# sd-logger.net
KiCad netlist of a schematic drawn in EAGLE
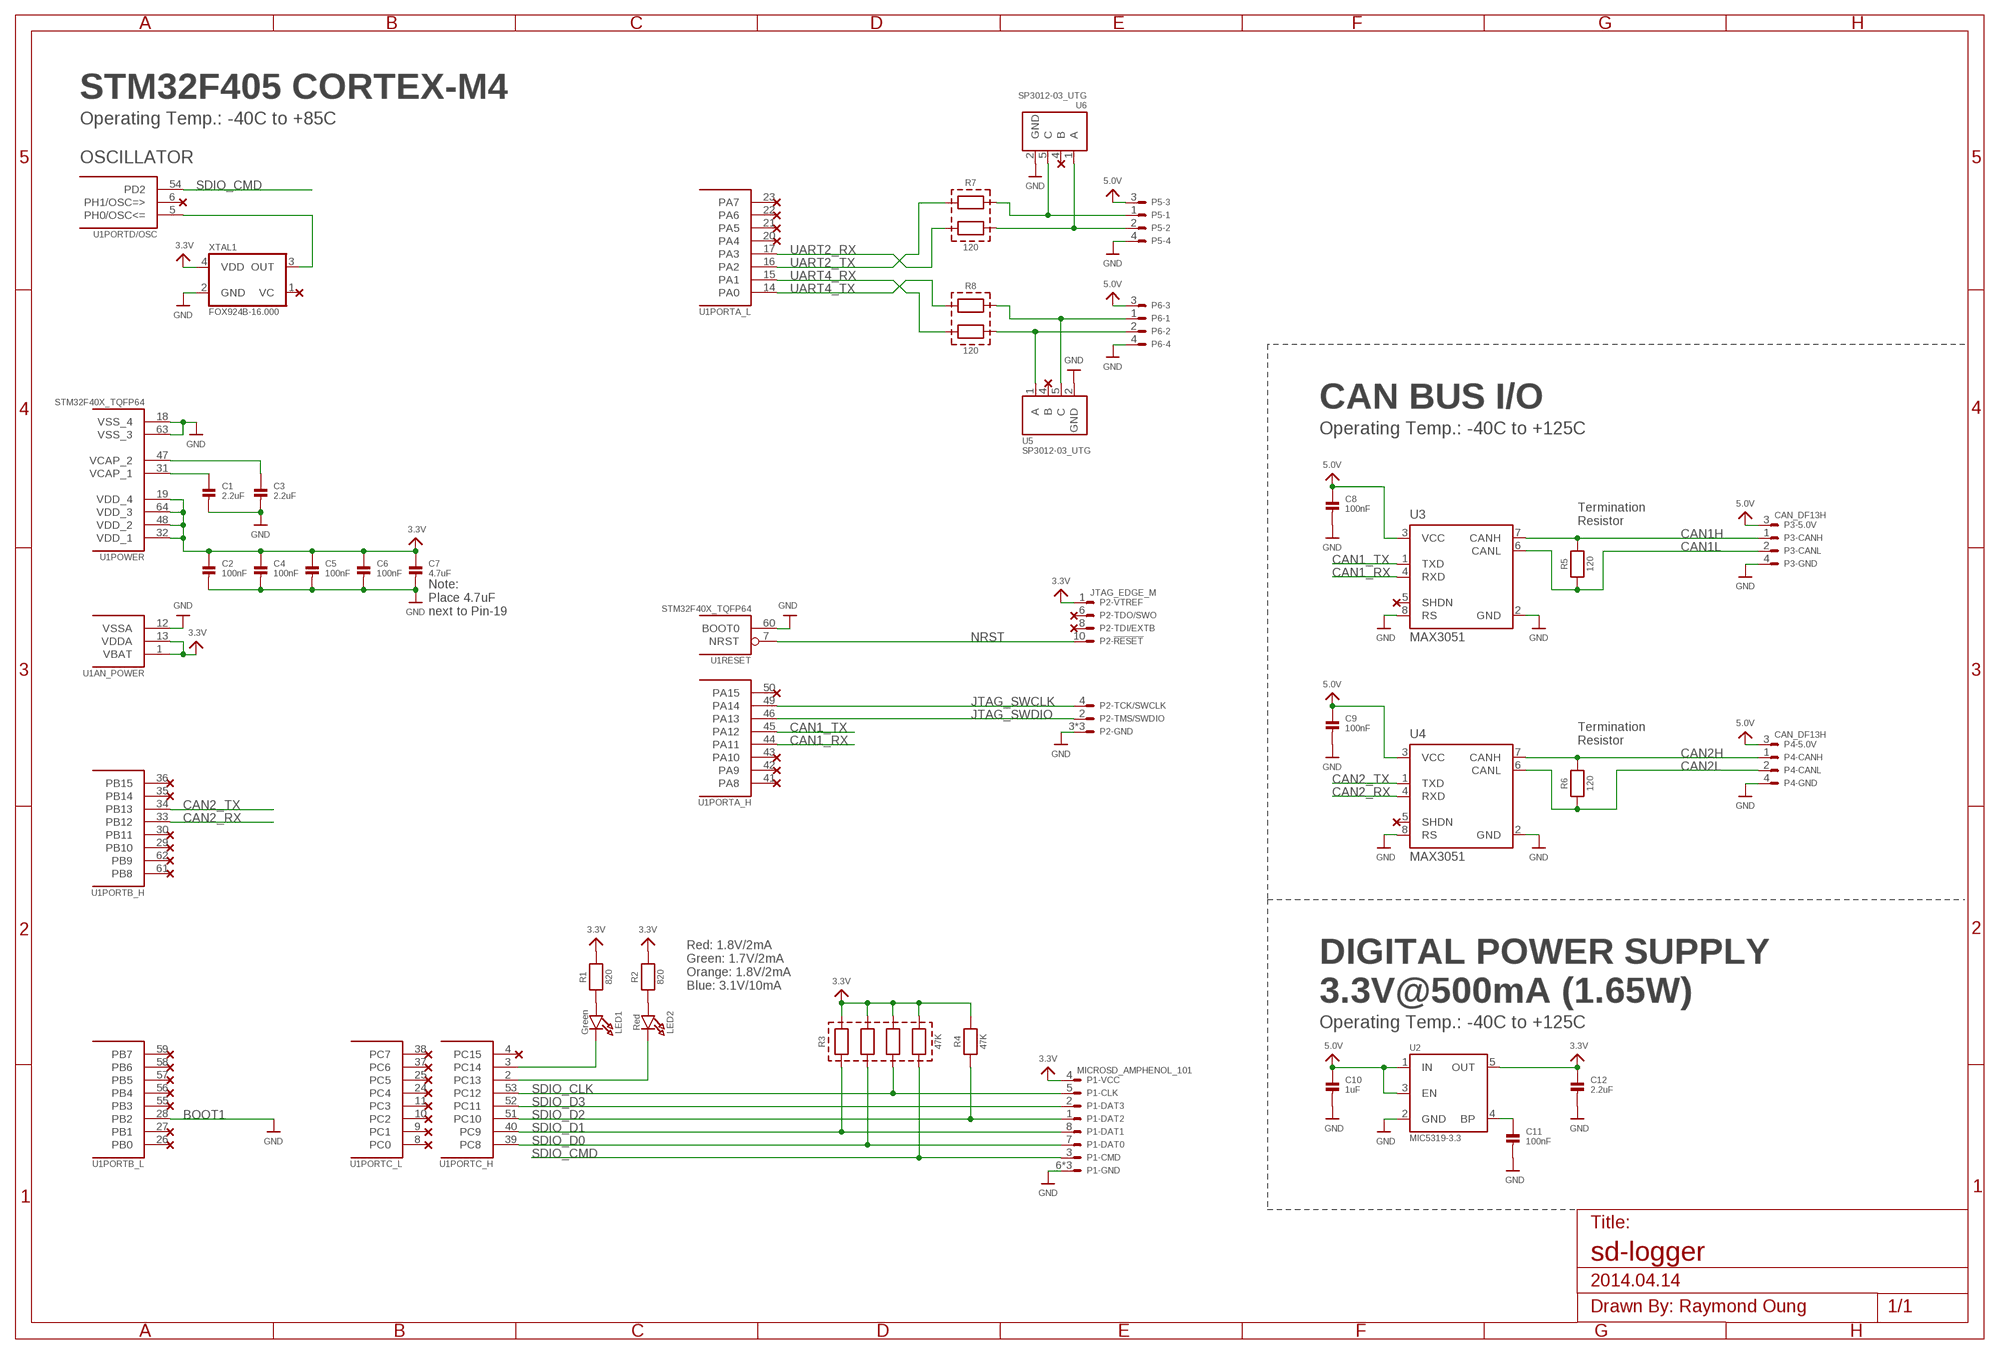
[diagram p0: schematic, sheet 1]

(export (version "E")
  (design (tool "Eeschema 10.0.6"))
  (components
    (comp (ref "C1")
      (value "2.2uF")
      (footprint "eagle-import:0402")
      (libsource (lib "eagle-import") (part "CAP_CERAMIC0402"))
    )
    (comp (ref "C2")
      (value "100nF")
      (footprint "eagle-import:0402")
      (libsource (lib "eagle-import") (part "CAP_CERAMIC0402"))
    )
    (comp (ref "C3")
      (value "2.2uF")
      (footprint "eagle-import:0402")
      (libsource (lib "eagle-import") (part "CAP_CERAMIC0402"))
    )
    (comp (ref "C4")
      (value "100nF")
      (footprint "eagle-import:0402")
      (libsource (lib "eagle-import") (part "CAP_CERAMIC0402"))
    )
    (comp (ref "C5")
      (value "100nF")
      (footprint "eagle-import:0402")
      (libsource (lib "eagle-import") (part "CAP_CERAMIC0402"))
    )
    (comp (ref "C6")
      (value "100nF")
      (footprint "eagle-import:0402")
      (libsource (lib "eagle-import") (part "CAP_CERAMIC0402"))
    )
    (comp (ref "C7")
      (value "4.7uF")
      (footprint "eagle-import:0402")
      (libsource (lib "eagle-import") (part "CAP_CERAMIC0402"))
    )
    (comp (ref "C8")
      (value "100nF")
      (footprint "eagle-import:0402")
      (libsource (lib "eagle-import") (part "CAP_CERAMIC0402"))
    )
    (comp (ref "C9")
      (value "100nF")
      (footprint "eagle-import:0402")
      (libsource (lib "eagle-import") (part "CAP_CERAMIC0402"))
    )
    (comp (ref "C10")
      (value "1uF")
      (footprint "eagle-import:0402")
      (libsource (lib "eagle-import") (part "CAP_CERAMIC0402"))
    )
    (comp (ref "C11")
      (value "100nF")
      (footprint "eagle-import:0402")
      (libsource (lib "eagle-import") (part "CAP_CERAMIC0402"))
    )
    (comp (ref "C12")
      (value "2.2uF")
      (footprint "eagle-import:0402")
      (libsource (lib "eagle-import") (part "CAP_CERAMIC0402"))
    )
    (comp (ref "LED1")
      (value "Green")
      (footprint "eagle-import:CHIPLED_0603")
      (libsource (lib "eagle-import") (part "LED_0603"))
    )
    (comp (ref "LED2")
      (value "Red")
      (footprint "eagle-import:CHIPLED_0603")
      (libsource (lib "eagle-import") (part "LED_0603"))
    )
    (comp (ref "P1")
      (value "MICROSD_AMPHENOL_101")
      (footprint "eagle-import:AMPHENOL_101-00660-68")
      (libsource (lib "eagle-import") (part "MICROSD_AMPHENOL_101"))
    )
    (comp (ref "P2")
      (value "JTAG_EDGE_M")
      (footprint "eagle-import:FTSH-105-01-XXX-DV-EDGE")
      (libsource (lib "eagle-import") (part "JTAG_EDGE_M"))
    )
    (comp (ref "P3")
      (value "CAN_DF13H")
      (footprint "eagle-import:DF13A-4P-1.25H")
      (libsource (lib "eagle-import") (part "CAN_DF13H"))
    )
    (comp (ref "P4")
      (value "CAN_DF13H")
      (footprint "eagle-import:DF13A-4P-1.25H")
      (libsource (lib "eagle-import") (part "CAN_DF13H"))
    )
    (comp (ref "P5")
      (value "M04_DF13H")
      (footprint "eagle-import:DF13A-4P-1.25H")
      (libsource (lib "eagle-import") (part "M04_DF13H"))
    )
    (comp (ref "P6")
      (value "M04_DF13H")
      (footprint "eagle-import:DF13A-4P-1.25H")
      (libsource (lib "eagle-import") (part "M04_DF13H"))
    )
    (comp (ref "R1")
      (value "820")
      (footprint "eagle-import:0402")
      (libsource (lib "eagle-import") (part "RESISTOR0402"))
    )
    (comp (ref "R2")
      (value "820")
      (footprint "eagle-import:0402")
      (libsource (lib "eagle-import") (part "RESISTOR0402"))
    )
    (comp (ref "R3")
      (value "47K")
      (footprint "eagle-import:EXBV8V")
      (libsource (lib "eagle-import") (part "RESISTOR4_0603X4"))
    )
    (comp (ref "R4")
      (value "47K")
      (footprint "eagle-import:0402")
      (libsource (lib "eagle-import") (part "RESISTOR0402"))
    )
    (comp (ref "R5")
      (value "120")
      (footprint "eagle-import:0603")
      (libsource (lib "eagle-import") (part "RESISTOR0603"))
    )
    (comp (ref "R6")
      (value "120")
      (footprint "eagle-import:0603")
      (libsource (lib "eagle-import") (part "RESISTOR0603"))
    )
    (comp (ref "R7")
      (value "120")
      (footprint "eagle-import:EXBV4V")
      (libsource (lib "eagle-import") (part "RESISTOR2_0603X2"))
    )
    (comp (ref "R8")
      (value "120")
      (footprint "eagle-import:EXBV4V")
      (libsource (lib "eagle-import") (part "RESISTOR2_0603X2"))
    )
    (comp (ref "U1")
      (value "STM32F40X_TQFP64")
      (footprint "eagle-import:TQFP64")
      (libsource (lib "eagle-import") (part "STM32F40X_TQFP64"))
    )
    (comp (ref "U2")
      (value "MIC5319-3.3")
      (footprint "eagle-import:SOT23-5")
      (libsource (lib "eagle-import") (part "MIC5319-3.3"))
    )
    (comp (ref "U3")
      (value "MAX3051")
      (footprint "eagle-import:SOT23-8")
      (libsource (lib "eagle-import") (part "MAX3051"))
    )
    (comp (ref "U4")
      (value "MAX3051")
      (footprint "eagle-import:SOT23-8")
      (libsource (lib "eagle-import") (part "MAX3051"))
    )
    (comp (ref "U5")
      (value "SP3012-03_UTG")
      (footprint "eagle-import:UDFN06")
      (libsource (lib "eagle-import") (part "SP3012-03_UTG"))
    )
    (comp (ref "U6")
      (value "SP3012-03_UTG")
      (footprint "eagle-import:UDFN06")
      (libsource (lib "eagle-import") (part "SP3012-03_UTG"))
    )
    (comp (ref "XTAL1")
      (value "FOX924B-16.000")
      (footprint "eagle-import:OSCILLATOR-5.0X3.2")
      (libsource (lib "eagle-import") (part "TCXO_5.0X3.2"))
    )
  )
  (nets
    (net (code "1") (name "/CAN1H") (class "Default")
      (node (ref "P3") (pin "1") (pinfunction "S_1") (pintype "passive"))
      (node (ref "R5") (pin "2") (pinfunction "2_2") (pintype "passive"))
      (node (ref "U3") (pin "7") (pinfunction "CANH_7") (pintype "bidirectional"))
    )
    (net (code "2") (name "/CAN1L") (class "Default")
      (node (ref "P3") (pin "2") (pinfunction "S_2") (pintype "passive"))
      (node (ref "R5") (pin "1") (pinfunction "1_1") (pintype "passive"))
      (node (ref "U3") (pin "6") (pinfunction "CANL_6") (pintype "bidirectional"))
    )
    (net (code "3") (name "/CAN1_RX") (class "Default")
      (node (ref "U1") (pin "44") (pinfunction "PA11_44") (pintype "bidirectional"))
      (node (ref "U3") (pin "4") (pinfunction "RXD_4") (pintype "bidirectional"))
    )
    (net (code "4") (name "/CAN1_TX") (class "Default")
      (node (ref "U1") (pin "45") (pinfunction "PA12_45") (pintype "bidirectional"))
      (node (ref "U3") (pin "1") (pinfunction "TXD_1") (pintype "bidirectional"))
    )
    (net (code "5") (name "/CAN2H") (class "Default")
      (node (ref "P4") (pin "1") (pinfunction "S_1") (pintype "passive"))
      (node (ref "R6") (pin "2") (pinfunction "2_2") (pintype "passive"))
      (node (ref "U4") (pin "7") (pinfunction "CANH_7") (pintype "bidirectional"))
    )
    (net (code "6") (name "/CAN2L") (class "Default")
      (node (ref "P4") (pin "2") (pinfunction "S_2") (pintype "passive"))
      (node (ref "R6") (pin "1") (pinfunction "1_1") (pintype "passive"))
      (node (ref "U4") (pin "6") (pinfunction "CANL_6") (pintype "bidirectional"))
    )
    (net (code "7") (name "/CAN2_RX") (class "Default")
      (node (ref "U1") (pin "33") (pinfunction "PB12_33") (pintype "bidirectional"))
      (node (ref "U4") (pin "4") (pinfunction "RXD_4") (pintype "bidirectional"))
    )
    (net (code "8") (name "/CAN2_TX") (class "Default")
      (node (ref "U1") (pin "34") (pinfunction "PB13_34") (pintype "bidirectional"))
      (node (ref "U4") (pin "1") (pinfunction "TXD_1") (pintype "bidirectional"))
    )
    (net (code "9") (name "/JTAG_SWCLK") (class "Default")
      (node (ref "P2") (pin "4") (pinfunction "S_4") (pintype "passive"))
      (node (ref "U1") (pin "49") (pinfunction "PA14_49") (pintype "bidirectional"))
    )
    (net (code "10") (name "/JTAG_SWDIO") (class "Default")
      (node (ref "P2") (pin "2") (pinfunction "S_2") (pintype "passive"))
      (node (ref "U1") (pin "46") (pinfunction "PA13_46") (pintype "bidirectional"))
    )
    (net (code "11") (name "/NRST") (class "Default")
      (node (ref "P2") (pin "10") (pinfunction "S_10") (pintype "passive"))
      (node (ref "U1") (pin "7") (pinfunction "NRST_7") (pintype "input"))
    )
    (net (code "12") (name "/SDIO_CLK") (class "Default")
      (node (ref "P1") (pin "5") (pinfunction "S_5") (pintype "passive"))
      (node (ref "R3") (pin "3") (pinfunction "3_3") (pintype "passive"))
      (node (ref "U1") (pin "53") (pinfunction "PC12_53") (pintype "bidirectional"))
    )
    (net (code "13") (name "/SDIO_CMD") (class "Default")
      (node (ref "P1") (pin "3") (pinfunction "S_3") (pintype "passive"))
      (node (ref "R3") (pin "4") (pinfunction "4_4") (pintype "passive"))
      (node (ref "U1") (pin "54") (pinfunction "PD2_54") (pintype "bidirectional"))
    )
    (net (code "14") (name "/SDIO_D0") (class "Default")
      (node (ref "P1") (pin "7") (pinfunction "S_7") (pintype "passive"))
      (node (ref "R3") (pin "2") (pinfunction "2_2") (pintype "passive"))
      (node (ref "U1") (pin "39") (pinfunction "PC8_39") (pintype "bidirectional"))
    )
    (net (code "15") (name "/SDIO_D1") (class "Default")
      (node (ref "P1") (pin "8") (pinfunction "S_8") (pintype "passive"))
      (node (ref "R3") (pin "1") (pinfunction "1_1") (pintype "passive"))
      (node (ref "U1") (pin "40") (pinfunction "PC9_40") (pintype "bidirectional"))
    )
    (net (code "16") (name "/SDIO_D2") (class "Default")
      (node (ref "P1") (pin "1") (pinfunction "S_1") (pintype "passive"))
      (node (ref "R4") (pin "1") (pinfunction "1_1") (pintype "passive"))
      (node (ref "U1") (pin "51") (pinfunction "PC10_51") (pintype "bidirectional"))
    )
    (net (code "17") (name "/SDIO_D3") (class "Default")
      (node (ref "P1") (pin "2") (pinfunction "S_2") (pintype "passive"))
      (node (ref "U1") (pin "52") (pinfunction "PC11_52") (pintype "bidirectional"))
    )
    (net (code "18") (name "/UART2_RX") (class "Default")
      (node (ref "R7") (pin "2") (pinfunction "2_2") (pintype "passive"))
      (node (ref "U1") (pin "17") (pinfunction "PA3_17") (pintype "bidirectional"))
    )
    (net (code "19") (name "/UART2_TX") (class "Default")
      (node (ref "R7") (pin "1") (pinfunction "1_1") (pintype "passive"))
      (node (ref "U1") (pin "16") (pinfunction "PA2_16") (pintype "bidirectional"))
    )
    (net (code "20") (name "/UART4_RX") (class "Default")
      (node (ref "R8") (pin "2") (pinfunction "2_2") (pintype "passive"))
      (node (ref "U1") (pin "15") (pinfunction "PA1_15") (pintype "bidirectional"))
    )
    (net (code "21") (name "/UART4_TX") (class "Default")
      (node (ref "R8") (pin "1") (pinfunction "1_1") (pintype "passive"))
      (node (ref "U1") (pin "14") (pinfunction "PA0_14") (pintype "bidirectional"))
    )
    (net (code "22") (name "3.3V") (class "Default")
      (node (ref "C12") (pin "1") (pinfunction "P$1_1") (pintype "passive"))
      (node (ref "C2") (pin "1") (pinfunction "P$1_1") (pintype "passive"))
      (node (ref "C4") (pin "1") (pinfunction "P$1_1") (pintype "passive"))
      (node (ref "C5") (pin "1") (pinfunction "P$1_1") (pintype "passive"))
      (node (ref "C6") (pin "1") (pinfunction "P$1_1") (pintype "passive"))
      (node (ref "C7") (pin "1") (pinfunction "P$1_1") (pintype "passive"))
      (node (ref "P1") (pin "4") (pinfunction "S_4") (pintype "passive"))
      (node (ref "P2") (pin "1") (pinfunction "S_1") (pintype "passive"))
      (node (ref "R1") (pin "2") (pinfunction "2_2") (pintype "passive"))
      (node (ref "R2") (pin "2") (pinfunction "2_2") (pintype "passive"))
      (node (ref "R3") (pin "5") (pinfunction "5_5") (pintype "passive"))
      (node (ref "R3") (pin "6") (pinfunction "6_6") (pintype "passive"))
      (node (ref "R3") (pin "7") (pinfunction "7_7") (pintype "passive"))
      (node (ref "R3") (pin "8") (pinfunction "8_8") (pintype "passive"))
      (node (ref "R4") (pin "2") (pinfunction "2_2") (pintype "passive"))
      (node (ref "U1") (pin "1") (pinfunction "VBAT_1") (pintype "power_in"))
      (node (ref "U1") (pin "13") (pinfunction "VDDA_13") (pintype "power_in"))
      (node (ref "U1") (pin "19") (pinfunction "VDD_4_19") (pintype "power_in"))
      (node (ref "U1") (pin "32") (pinfunction "VDD_1_32") (pintype "power_in"))
      (node (ref "U1") (pin "48") (pinfunction "VDD_2_48") (pintype "power_in"))
      (node (ref "U1") (pin "64") (pinfunction "VDD_3_64") (pintype "power_in"))
      (node (ref "U2") (pin "5") (pinfunction "OUT_5") (pintype "bidirectional"))
      (node (ref "XTAL1") (pin "4") (pinfunction "VDD_4") (pintype "bidirectional"))
    )
    (net (code "23") (name "5.0V") (class "Default")
      (node (ref "C10") (pin "1") (pinfunction "P$1_1") (pintype "passive"))
      (node (ref "C8") (pin "1") (pinfunction "P$1_1") (pintype "passive"))
      (node (ref "C9") (pin "1") (pinfunction "P$1_1") (pintype "passive"))
      (node (ref "P3") (pin "3") (pinfunction "S_3") (pintype "passive"))
      (node (ref "P4") (pin "3") (pinfunction "S_3") (pintype "passive"))
      (node (ref "P5") (pin "3") (pinfunction "S_3") (pintype "passive"))
      (node (ref "P6") (pin "3") (pinfunction "S_3") (pintype "passive"))
      (node (ref "U2") (pin "1") (pinfunction "IN_1") (pintype "bidirectional"))
      (node (ref "U2") (pin "3") (pinfunction "EN_3") (pintype "bidirectional"))
      (node (ref "U3") (pin "3") (pinfunction "VCC_3") (pintype "bidirectional"))
      (node (ref "U4") (pin "3") (pinfunction "VCC_3") (pintype "bidirectional"))
    )
    (net (code "24") (name "GND") (class "Default")
      (node (ref "C1") (pin "2") (pinfunction "P$2_2") (pintype "passive"))
      (node (ref "C10") (pin "2") (pinfunction "P$2_2") (pintype "passive"))
      (node (ref "C11") (pin "2") (pinfunction "P$2_2") (pintype "passive"))
      (node (ref "C12") (pin "2") (pinfunction "P$2_2") (pintype "passive"))
      (node (ref "C2") (pin "2") (pinfunction "P$2_2") (pintype "passive"))
      (node (ref "C3") (pin "2") (pinfunction "P$2_2") (pintype "passive"))
      (node (ref "C4") (pin "2") (pinfunction "P$2_2") (pintype "passive"))
      (node (ref "C5") (pin "2") (pinfunction "P$2_2") (pintype "passive"))
      (node (ref "C6") (pin "2") (pinfunction "P$2_2") (pintype "passive"))
      (node (ref "C7") (pin "2") (pinfunction "P$2_2") (pintype "passive"))
      (node (ref "C8") (pin "2") (pinfunction "P$2_2") (pintype "passive"))
      (node (ref "C9") (pin "2") (pinfunction "P$2_2") (pintype "passive"))
      (node (ref "P1") (pin "6") (pinfunction "S_6") (pintype "passive"))
      (node (ref "P1") (pin "GND1") (pinfunction "S_GND1") (pintype "passive"))
      (node (ref "P1") (pin "GND3") (pinfunction "S_GND3") (pintype "passive"))
      (node (ref "P2") (pin "3") (pinfunction "S_3") (pintype "passive"))
      (node (ref "P2") (pin "5") (pinfunction "S_5") (pintype "passive"))
      (node (ref "P2") (pin "9") (pinfunction "S_9") (pintype "passive"))
      (node (ref "P3") (pin "4") (pinfunction "S_4") (pintype "passive"))
      (node (ref "P4") (pin "4") (pinfunction "S_4") (pintype "passive"))
      (node (ref "P5") (pin "4") (pinfunction "S_4") (pintype "passive"))
      (node (ref "P6") (pin "4") (pinfunction "S_4") (pintype "passive"))
      (node (ref "U1") (pin "12") (pinfunction "VSSA_12") (pintype "power_in"))
      (node (ref "U1") (pin "18") (pinfunction "VSS_4_18") (pintype "power_in"))
      (node (ref "U1") (pin "28") (pinfunction "PB2_28") (pintype "bidirectional"))
      (node (ref "U1") (pin "60") (pinfunction "BOOT0_60") (pintype "input"))
      (node (ref "U1") (pin "63") (pinfunction "VSS_3_63") (pintype "power_in"))
      (node (ref "U2") (pin "2") (pinfunction "GND_2") (pintype "bidirectional"))
      (node (ref "U3") (pin "2") (pinfunction "GND_2") (pintype "bidirectional"))
      (node (ref "U3") (pin "8") (pinfunction "RS_8") (pintype "bidirectional"))
      (node (ref "U4") (pin "2") (pinfunction "GND_2") (pintype "bidirectional"))
      (node (ref "U4") (pin "8") (pinfunction "RS_8") (pintype "bidirectional"))
      (node (ref "U5") (pin "2") (pinfunction "GND_2") (pintype "power_in"))
      (node (ref "U6") (pin "2") (pinfunction "GND_2") (pintype "power_in"))
      (node (ref "XTAL1") (pin "2") (pinfunction "GND_2") (pintype "bidirectional"))
    )
    (net (code "25") (name "Net-(C1-P$1)") (class "Default")
      (node (ref "C1") (pin "1") (pinfunction "P$1_1") (pintype "passive"))
      (node (ref "U1") (pin "31") (pinfunction "VCAP_1_31") (pintype "power_in"))
    )
    (net (code "26") (name "Net-(C3-P$1)") (class "Default")
      (node (ref "C3") (pin "1") (pinfunction "P$1_1") (pintype "passive"))
      (node (ref "U1") (pin "47") (pinfunction "VCAP_2_47") (pintype "power_in"))
    )
    (net (code "27") (name "Net-(C11-P$1)") (class "Default")
      (node (ref "C11") (pin "1") (pinfunction "P$1_1") (pintype "passive"))
      (node (ref "U2") (pin "4") (pinfunction "BP_4") (pintype "bidirectional"))
    )
    (net (code "28") (name "Net-(LED1-PadA)") (class "Default")
      (node (ref "LED1") (pin "A") (pinfunction "A_A") (pintype "passive"))
      (node (ref "R1") (pin "1") (pinfunction "1_1") (pintype "passive"))
    )
    (net (code "29") (name "Net-(LED2-PadA)") (class "Default")
      (node (ref "LED2") (pin "A") (pinfunction "A_A") (pintype "passive"))
      (node (ref "R2") (pin "1") (pinfunction "1_1") (pintype "passive"))
    )
    (net (code "30") (name "Net-(P5A-S)") (class "Default")
      (node (ref "P5") (pin "1") (pinfunction "S_1") (pintype "passive"))
      (node (ref "R7") (pin "4") (pinfunction "4_4") (pintype "passive"))
      (node (ref "U6") (pin "5") (pinfunction "C_5") (pintype "bidirectional"))
    )
    (net (code "31") (name "Net-(P5B-S)") (class "Default")
      (node (ref "P5") (pin "2") (pinfunction "S_2") (pintype "passive"))
      (node (ref "R7") (pin "3") (pinfunction "3_3") (pintype "passive"))
      (node (ref "U6") (pin "1") (pinfunction "A_1") (pintype "bidirectional"))
    )
    (net (code "32") (name "Net-(P6A-S)") (class "Default")
      (node (ref "P6") (pin "1") (pinfunction "S_1") (pintype "passive"))
      (node (ref "R8") (pin "4") (pinfunction "4_4") (pintype "passive"))
      (node (ref "U5") (pin "5") (pinfunction "C_5") (pintype "bidirectional"))
    )
    (net (code "33") (name "Net-(P6B-S)") (class "Default")
      (node (ref "P6") (pin "2") (pinfunction "S_2") (pintype "passive"))
      (node (ref "R8") (pin "3") (pinfunction "3_3") (pintype "passive"))
      (node (ref "U5") (pin "1") (pinfunction "A_1") (pintype "bidirectional"))
    )
    (net (code "34") (name "Net-(U1F-PC13)") (class "Default")
      (node (ref "LED2") (pin "C") (pinfunction "C_C") (pintype "passive"))
      (node (ref "U1") (pin "2") (pinfunction "PC13_2") (pintype "bidirectional"))
    )
    (net (code "35") (name "Net-(U1F-PC14)") (class "Default")
      (node (ref "LED1") (pin "C") (pinfunction "C_C") (pintype "passive"))
      (node (ref "U1") (pin "3") (pinfunction "PC14_3") (pintype "bidirectional"))
    )
    (net (code "36") (name "Net-(U1H-PH0{slash}OSC<=)") (class "Default")
      (node (ref "U1") (pin "5") (pinfunction "PH0/OSC<=_5") (pintype "bidirectional"))
      (node (ref "XTAL1") (pin "3") (pinfunction "OUT_3") (pintype "bidirectional"))
    )
    (net (code "37") (name "unconnected-(P2D-S-Pad8)") (class "Default")
      (node (ref "P2") (pin "8") (pinfunction "S_8") (pintype "passive"))
    )
    (net (code "38") (name "unconnected-(P2E-S-Pad6)") (class "Default")
      (node (ref "P2") (pin "6") (pinfunction "S_6") (pintype "passive"))
    )
    (net (code "39") (name "unconnected-(U1B-PA8-Pad41)") (class "Default")
      (node (ref "U1") (pin "41") (pinfunction "PA8_41") (pintype "bidirectional"))
    )
    (net (code "40") (name "unconnected-(U1B-PA9-Pad42)") (class "Default")
      (node (ref "U1") (pin "42") (pinfunction "PA9_42") (pintype "bidirectional"))
    )
    (net (code "41") (name "unconnected-(U1B-PA10-Pad43)") (class "Default")
      (node (ref "U1") (pin "43") (pinfunction "PA10_43") (pintype "bidirectional"))
    )
    (net (code "42") (name "unconnected-(U1B-PA15-Pad50)") (class "Default")
      (node (ref "U1") (pin "50") (pinfunction "PA15_50") (pintype "bidirectional"))
    )
    (net (code "43") (name "unconnected-(U1C-PA4-Pad20)") (class "Default")
      (node (ref "U1") (pin "20") (pinfunction "PA4_20") (pintype "bidirectional"))
    )
    (net (code "44") (name "unconnected-(U1C-PA5-Pad21)") (class "Default")
      (node (ref "U1") (pin "21") (pinfunction "PA5_21") (pintype "bidirectional"))
    )
    (net (code "45") (name "unconnected-(U1C-PA6-Pad22)") (class "Default")
      (node (ref "U1") (pin "22") (pinfunction "PA6_22") (pintype "bidirectional"))
    )
    (net (code "46") (name "unconnected-(U1C-PA7-Pad23)") (class "Default")
      (node (ref "U1") (pin "23") (pinfunction "PA7_23") (pintype "bidirectional"))
    )
    (net (code "47") (name "unconnected-(U1D-PB8-Pad61)") (class "Default")
      (node (ref "U1") (pin "61") (pinfunction "PB8_61") (pintype "bidirectional"))
    )
    (net (code "48") (name "unconnected-(U1D-PB9-Pad62)") (class "Default")
      (node (ref "U1") (pin "62") (pinfunction "PB9_62") (pintype "bidirectional"))
    )
    (net (code "49") (name "unconnected-(U1D-PB10-Pad29)") (class "Default")
      (node (ref "U1") (pin "29") (pinfunction "PB10_29") (pintype "bidirectional"))
    )
    (net (code "50") (name "unconnected-(U1D-PB11-Pad30)") (class "Default")
      (node (ref "U1") (pin "30") (pinfunction "PB11_30") (pintype "bidirectional"))
    )
    (net (code "51") (name "unconnected-(U1D-PB14-Pad35)") (class "Default")
      (node (ref "U1") (pin "35") (pinfunction "PB14_35") (pintype "bidirectional"))
    )
    (net (code "52") (name "unconnected-(U1D-PB15-Pad36)") (class "Default")
      (node (ref "U1") (pin "36") (pinfunction "PB15_36") (pintype "bidirectional"))
    )
    (net (code "53") (name "unconnected-(U1E-PB0-Pad26)") (class "Default")
      (node (ref "U1") (pin "26") (pinfunction "PB0_26") (pintype "bidirectional"))
    )
    (net (code "54") (name "unconnected-(U1E-PB1-Pad27)") (class "Default")
      (node (ref "U1") (pin "27") (pinfunction "PB1_27") (pintype "bidirectional"))
    )
    (net (code "55") (name "unconnected-(U1E-PB3-Pad55)") (class "Default")
      (node (ref "U1") (pin "55") (pinfunction "PB3_55") (pintype "bidirectional"))
    )
    (net (code "56") (name "unconnected-(U1E-PB4-Pad56)") (class "Default")
      (node (ref "U1") (pin "56") (pinfunction "PB4_56") (pintype "bidirectional"))
    )
    (net (code "57") (name "unconnected-(U1E-PB5-Pad57)") (class "Default")
      (node (ref "U1") (pin "57") (pinfunction "PB5_57") (pintype "bidirectional"))
    )
    (net (code "58") (name "unconnected-(U1E-PB6-Pad58)") (class "Default")
      (node (ref "U1") (pin "58") (pinfunction "PB6_58") (pintype "bidirectional"))
    )
    (net (code "59") (name "unconnected-(U1E-PB7-Pad59)") (class "Default")
      (node (ref "U1") (pin "59") (pinfunction "PB7_59") (pintype "bidirectional"))
    )
    (net (code "60") (name "unconnected-(U1F-PC15-Pad4)") (class "Default")
      (node (ref "U1") (pin "4") (pinfunction "PC15_4") (pintype "bidirectional"))
    )
    (net (code "61") (name "unconnected-(U1G-PC0-Pad8)") (class "Default")
      (node (ref "U1") (pin "8") (pinfunction "PC0_8") (pintype "bidirectional"))
    )
    (net (code "62") (name "unconnected-(U1G-PC1-Pad9)") (class "Default")
      (node (ref "U1") (pin "9") (pinfunction "PC1_9") (pintype "bidirectional"))
    )
    (net (code "63") (name "unconnected-(U1G-PC2-Pad10)") (class "Default")
      (node (ref "U1") (pin "10") (pinfunction "PC2_10") (pintype "bidirectional"))
    )
    (net (code "64") (name "unconnected-(U1G-PC3-Pad11)") (class "Default")
      (node (ref "U1") (pin "11") (pinfunction "PC3_11") (pintype "bidirectional"))
    )
    (net (code "65") (name "unconnected-(U1G-PC4-Pad24)") (class "Default")
      (node (ref "U1") (pin "24") (pinfunction "PC4_24") (pintype "bidirectional"))
    )
    (net (code "66") (name "unconnected-(U1G-PC5-Pad25)") (class "Default")
      (node (ref "U1") (pin "25") (pinfunction "PC5_25") (pintype "bidirectional"))
    )
    (net (code "67") (name "unconnected-(U1G-PC6-Pad37)") (class "Default")
      (node (ref "U1") (pin "37") (pinfunction "PC6_37") (pintype "bidirectional"))
    )
    (net (code "68") (name "unconnected-(U1G-PC7-Pad38)") (class "Default")
      (node (ref "U1") (pin "38") (pinfunction "PC7_38") (pintype "bidirectional"))
    )
    (net (code "69") (name "unconnected-(U1H-PH1{slash}OSC=>-Pad6)") (class "Default")
      (node (ref "U1") (pin "6") (pinfunction "PH1/OSC=>_6") (pintype "bidirectional"))
    )
    (net (code "70") (name "unconnected-(U3-SHDN-Pad5)") (class "Default")
      (node (ref "U3") (pin "5") (pinfunction "SHDN_5") (pintype "bidirectional"))
    )
    (net (code "71") (name "unconnected-(U4-SHDN-Pad5)") (class "Default")
      (node (ref "U4") (pin "5") (pinfunction "SHDN_5") (pintype "bidirectional"))
    )
    (net (code "72") (name "unconnected-(U5-B-Pad4)") (class "Default")
      (node (ref "U5") (pin "4") (pinfunction "B_4") (pintype "bidirectional"))
    )
    (net (code "73") (name "unconnected-(U6-B-Pad4)") (class "Default")
      (node (ref "U6") (pin "4") (pinfunction "B_4") (pintype "bidirectional"))
    )
    (net (code "74") (name "unconnected-(XTAL1-VC-Pad1)") (class "Default")
      (node (ref "XTAL1") (pin "1") (pinfunction "VC_1") (pintype "bidirectional"))
    )
  )
)
